# PERIPHERAL.net
KiCad netlist of a schematic drawn in Altium Designer
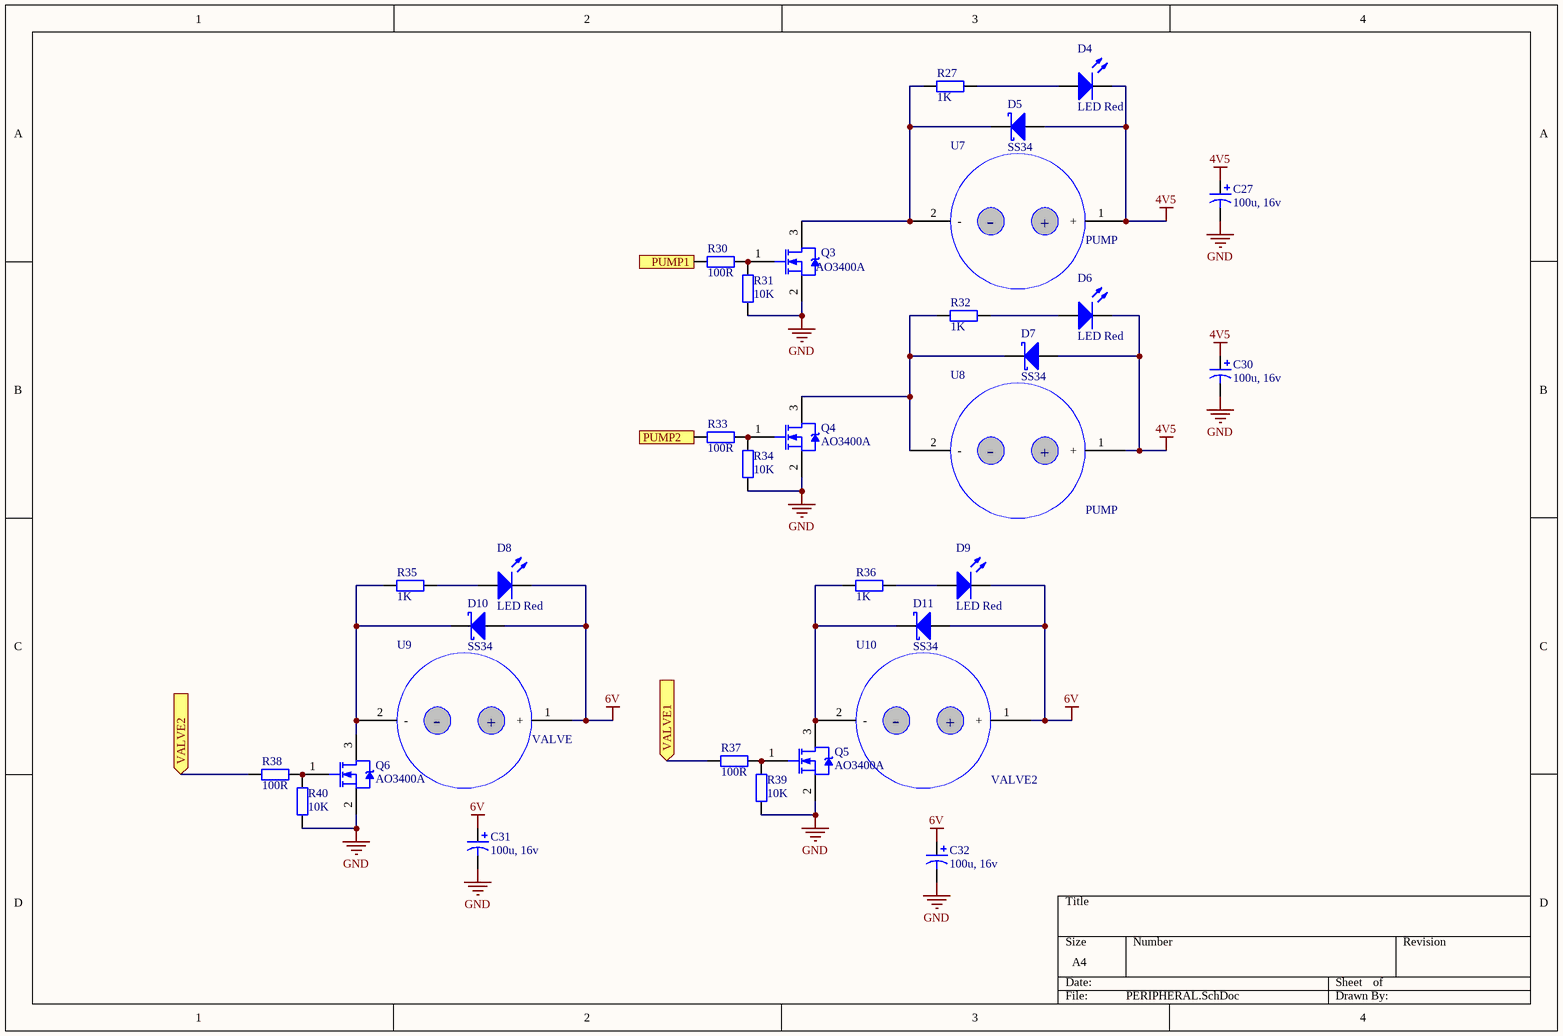
[diagram p0: PERIPHERAL.SchDoc]

(export (version "E")
  (design (tool "Eeschema 10.0.6"))
  (components
    (comp (ref "C27")
      (value "100u, 16v")
      (footprint "CAP-ALU-SMD-D")
      (description "CAP ALUM 100UF 20% 16V SMD")
      (libsource (lib "capacitor") (part "UWT1C101MCL1GB"))
    )
    (comp (ref "C30")
      (value "100u, 16v")
      (footprint "CAP-ALU-SMD-D")
      (description "CAP ALUM 100UF 20% 16V SMD")
      (libsource (lib "capacitor") (part "UWT1C101MCL1GB"))
    )
    (comp (ref "C31")
      (value "100u, 16v")
      (footprint "CAP-ALU-SMD-D")
      (description "CAP ALUM 100UF 20% 16V SMD")
      (libsource (lib "capacitor") (part "UWT1C101MCL1GB"))
    )
    (comp (ref "C32")
      (value "100u, 16v")
      (footprint "CAP-ALU-SMD-D")
      (description "CAP ALUM 100UF 20% 16V SMD")
      (libsource (lib "capacitor") (part "UWT1C101MCL1GB"))
    )
    (comp (ref "D4")
      (value "LED Red")
      (footprint "LED-0805-Red")
      (description "Lite-On LED Red 0603")
      (libsource (lib "diode") (part "LTST-C190KRKT"))
    )
    (comp (ref "D5")
      (value "SS34")
      (footprint "DIO-SMD-106")
      (description "Schottky Diode 40V 3A SMA")
      (libsource (lib "diode") (part "SS34"))
    )
    (comp (ref "D6")
      (value "LED Red")
      (footprint "LED-0805-Red")
      (description "Lite-On LED Red 0603")
      (libsource (lib "diode") (part "LTST-C190KRKT"))
    )
    (comp (ref "D7")
      (value "SS34")
      (footprint "DIO-SMD-106")
      (description "Schottky Diode 40V 3A SMA")
      (libsource (lib "diode") (part "SS34"))
    )
    (comp (ref "D8")
      (value "LED Red")
      (footprint "LED-0805-Red")
      (description "Lite-On LED Red 0603")
      (libsource (lib "diode") (part "LTST-C190KRKT"))
    )
    (comp (ref "D9")
      (value "LED Red")
      (footprint "LED-0805-Red")
      (description "Lite-On LED Red 0603")
      (libsource (lib "diode") (part "LTST-C190KRKT"))
    )
    (comp (ref "D10")
      (value "SS34")
      (footprint "DIO-SMD-106")
      (description "Schottky Diode 40V 3A SMA")
      (libsource (lib "diode") (part "SS34"))
    )
    (comp (ref "D11")
      (value "SS34")
      (footprint "DIO-SMD-106")
      (description "Schottky Diode 40V 3A SMA")
      (libsource (lib "diode") (part "SS34"))
    )
    (comp (ref "Q3")
      (value "AO3400A")
      (footprint "SOT-23-3L_AOS")
      (description "MOSFET N-CH 25V 5.8A SOT23")
      (libsource (lib "fet") (part "IRFML8244TRPBF"))
    )
    (comp (ref "Q4")
      (value "AO3400A")
      (footprint "SOT-23-3L_AOS-L")
      (description "MOSFET N-CH 25V 5.8A SOT23")
      (libsource (lib "fet") (part "IRFML8244TRPBF"))
    )
    (comp (ref "Q5")
      (value "AO3400A")
      (footprint "SOT-23-3L_AOS-L")
      (description "MOSFET N-CH 25V 5.8A SOT23")
      (libsource (lib "fet") (part "IRFML8244TRPBF"))
    )
    (comp (ref "Q6")
      (value "AO3400A")
      (footprint "SOT-23-3L_AOS-L")
      (description "MOSFET N-CH 25V 5.8A SOT23")
      (libsource (lib "fet") (part "IRFML8244TRPBF"))
    )
    (comp (ref "R27")
      (value "1K")
      (footprint "RES-SMD-0603")
      (description "Yageo RES 1K 5% 1/10W 0603")
      (fields (field (name "Comment") "RES 1K 5% 1/10W 0603"))
      (libsource (lib "resistor") (part "RC0603JR-071KL"))
    )
    (comp (ref "R30")
      (value "100R")
      (footprint "RES-SMD-0603")
      (description "Yageo RES 100R 5% 1/10W 0603")
      (fields (field (name "Comment") "RES 100R 5% 1/10W 0603"))
      (libsource (lib "resistor") (part "RC0603JR-07100RL"))
    )
    (comp (ref "R31")
      (value "10K")
      (footprint "RES-SMD-0603")
      (description "Yageo RES 10K 5% 1/10W 0603")
      (fields (field (name "Comment") "RES 10K 5% 1/10W 0603"))
      (libsource (lib "resistor") (part "RC0603JR-0710KL"))
    )
    (comp (ref "R32")
      (value "1K")
      (footprint "RES-SMD-0603")
      (description "Yageo RES 1K 5% 1/10W 0603")
      (fields (field (name "Comment") "RES 1K 5% 1/10W 0603"))
      (libsource (lib "resistor") (part "RC0603JR-071KL"))
    )
    (comp (ref "R33")
      (value "100R")
      (footprint "RES-SMD-0603")
      (description "Yageo RES 100R 5% 1/10W 0603")
      (fields (field (name "Comment") "RES 100R 5% 1/10W 0603"))
      (libsource (lib "resistor") (part "RC0603JR-07100RL"))
    )
    (comp (ref "R34")
      (value "10K")
      (footprint "RES-SMD-0603")
      (description "Yageo RES 10K 5% 1/10W 0603")
      (fields (field (name "Comment") "RES 10K 5% 1/10W 0603"))
      (libsource (lib "resistor") (part "RC0603JR-0710KL"))
    )
    (comp (ref "R35")
      (value "1K")
      (footprint "RES-SMD-0603")
      (description "Yageo RES 1K 5% 1/10W 0603")
      (fields (field (name "Comment") "RES 1K 5% 1/10W 0603"))
      (libsource (lib "resistor") (part "RC0603JR-071KL"))
    )
    (comp (ref "R36")
      (value "1K")
      (footprint "RES-SMD-0603")
      (description "Yageo RES 1K 5% 1/10W 0603")
      (fields (field (name "Comment") "RES 1K 5% 1/10W 0603"))
      (libsource (lib "resistor") (part "RC0603JR-071KL"))
    )
    (comp (ref "R37")
      (value "100R")
      (footprint "RES-SMD-0603")
      (description "Yageo RES 100R 5% 1/10W 0603")
      (fields (field (name "Comment") "RES 100R 5% 1/10W 0603"))
      (libsource (lib "resistor") (part "RC0603JR-07100RL"))
    )
    (comp (ref "R38")
      (value "100R")
      (footprint "RES-SMD-0603")
      (description "Yageo RES 100R 5% 1/10W 0603")
      (fields (field (name "Comment") "RES 100R 5% 1/10W 0603"))
      (libsource (lib "resistor") (part "RC0603JR-07100RL"))
    )
    (comp (ref "R39")
      (value "10K")
      (footprint "RES-SMD-0603")
      (description "Yageo RES 10K 5% 1/10W 0603")
      (fields (field (name "Comment") "RES 10K 5% 1/10W 0603"))
      (libsource (lib "resistor") (part "RC0603JR-0710KL"))
    )
    (comp (ref "R40")
      (value "10K")
      (footprint "RES-SMD-0603")
      (description "Yageo RES 10K 5% 1/10W 0603")
      (fields (field (name "Comment") "RES 10K 5% 1/10W 0603"))
      (libsource (lib "resistor") (part "RC0603JR-0710KL"))
    )
    (comp (ref "U7")
      (value "PUMP")
      (footprint "Pump")
      (description "Connector Header 2 Position 6.35mm Solder Straight Thru-Hole 2 Terminal 1 Port MLX-Series")
      (fields (field (name "MANUFACTURER") "Molex") (field (name "MANUFACTURER PART NUMBER") "10-84-4022"))
      (libsource (lib "LIB_PRESSURE") (part "A5F083"))
    )
    (comp (ref "U8")
      (value "PUMP")
      (footprint "Pump")
      (description "Connector Header 2 Position 6.35mm Solder Straight Thru-Hole 2 Terminal 1 Port MLX-Series")
      (fields (field (name "MANUFACTURER") "Molex") (field (name "MANUFACTURER PART NUMBER") "10-84-4022"))
      (libsource (lib "LIB_PRESSURE") (part "A5F083"))
    )
    (comp (ref "U9")
      (value "VALVE")
      (footprint "VALVE")
      (description "Connector Header 2 Position 6.35mm Solder Straight Thru-Hole 2 Terminal 1 Port MLX-Series")
      (fields (field (name "MANUFACTURER") "Molex") (field (name "MANUFACTURER PART NUMBER") "10-84-4022"))
      (libsource (lib "LIB_PRESSURE") (part "A5F083"))
    )
    (comp (ref "U10")
      (value "VALVE2")
      (footprint "VALVE")
      (description "Connector Header 2 Position 6.35mm Solder Straight Thru-Hole 2 Terminal 1 Port MLX-Series")
      (fields (field (name "MANUFACTURER") "Molex") (field (name "MANUFACTURER PART NUMBER") "10-84-4022"))
      (libsource (lib "LIB_PRESSURE") (part "A5F083"))
    )
  )
  (nets
    (net (code "1") (name "/PUMP1") (class "Default")
      (node (ref "R30") (pin "1") (pinfunction "1_1") (pintype "passive"))
    )
    (net (code "2") (name "/PUMP2") (class "Default")
      (node (ref "R33") (pin "1") (pinfunction "1_1") (pintype "passive"))
    )
    (net (code "3") (name "/VALVE1") (class "Default")
      (node (ref "R37") (pin "1") (pinfunction "1_1") (pintype "passive"))
    )
    (net (code "4") (name "/VALVE2") (class "Default")
      (node (ref "R38") (pin "1") (pinfunction "1_1") (pintype "passive"))
    )
    (net (code "5") (name "4V5") (class "Default")
      (node (ref "C27") (pin "1") (pinfunction "1_1") (pintype "passive"))
      (node (ref "C30") (pin "1") (pinfunction "1_1") (pintype "passive"))
      (node (ref "D4") (pin "2") (pinfunction "K_2") (pintype "passive"))
      (node (ref "D5") (pin "1") (pinfunction "A_1") (pintype "passive"))
      (node (ref "D6") (pin "2") (pinfunction "K_2") (pintype "passive"))
      (node (ref "D7") (pin "1") (pinfunction "A_1") (pintype "passive"))
      (node (ref "U7") (pin "1") (pinfunction "+_1") (pintype "passive"))
      (node (ref "U8") (pin "1") (pinfunction "+_1") (pintype "passive"))
    )
    (net (code "6") (name "6V") (class "Default")
      (node (ref "C31") (pin "1") (pinfunction "1_1") (pintype "passive"))
      (node (ref "C32") (pin "1") (pinfunction "1_1") (pintype "passive"))
      (node (ref "D10") (pin "1") (pinfunction "A_1") (pintype "passive"))
      (node (ref "D11") (pin "1") (pinfunction "A_1") (pintype "passive"))
      (node (ref "D8") (pin "2") (pinfunction "K_2") (pintype "passive"))
      (node (ref "D9") (pin "2") (pinfunction "K_2") (pintype "passive"))
      (node (ref "U10") (pin "1") (pinfunction "+_1") (pintype "passive"))
      (node (ref "U9") (pin "1") (pinfunction "+_1") (pintype "passive"))
    )
    (net (code "7") (name "GND") (class "Default")
      (node (ref "C27") (pin "2") (pinfunction "2_2") (pintype "passive"))
      (node (ref "C30") (pin "2") (pinfunction "2_2") (pintype "passive"))
      (node (ref "C31") (pin "2") (pinfunction "2_2") (pintype "passive"))
      (node (ref "C32") (pin "2") (pinfunction "2_2") (pintype "passive"))
      (node (ref "Q3") (pin "2") (pinfunction "S_2") (pintype "passive"))
      (node (ref "Q4") (pin "2") (pinfunction "S_2") (pintype "passive"))
      (node (ref "Q5") (pin "2") (pinfunction "S_2") (pintype "passive"))
      (node (ref "Q6") (pin "2") (pinfunction "S_2") (pintype "passive"))
      (node (ref "R31") (pin "1") (pinfunction "1_1") (pintype "passive"))
      (node (ref "R34") (pin "1") (pinfunction "1_1") (pintype "passive"))
      (node (ref "R39") (pin "1") (pinfunction "1_1") (pintype "passive"))
      (node (ref "R40") (pin "1") (pinfunction "1_1") (pintype "passive"))
    )
    (net (code "8") (name "Net-(D4-A)") (class "Default")
      (node (ref "D4") (pin "1") (pinfunction "A_1") (pintype "passive"))
      (node (ref "R27") (pin "2") (pinfunction "2_2") (pintype "passive"))
    )
    (net (code "9") (name "Net-(D5-K)") (class "Default")
      (node (ref "D5") (pin "2") (pinfunction "K_2") (pintype "passive"))
      (node (ref "Q3") (pin "3") (pinfunction "D_3") (pintype "passive"))
      (node (ref "R27") (pin "1") (pinfunction "1_1") (pintype "passive"))
      (node (ref "U7") (pin "2") (pinfunction "-_2") (pintype "passive"))
    )
    (net (code "10") (name "Net-(D6-A)") (class "Default")
      (node (ref "D6") (pin "1") (pinfunction "A_1") (pintype "passive"))
      (node (ref "R32") (pin "2") (pinfunction "2_2") (pintype "passive"))
    )
    (net (code "11") (name "Net-(D7-K)") (class "Default")
      (node (ref "D7") (pin "2") (pinfunction "K_2") (pintype "passive"))
      (node (ref "Q4") (pin "3") (pinfunction "D_3") (pintype "passive"))
      (node (ref "R32") (pin "1") (pinfunction "1_1") (pintype "passive"))
      (node (ref "U8") (pin "2") (pinfunction "-_2") (pintype "passive"))
    )
    (net (code "12") (name "Net-(D8-A)") (class "Default")
      (node (ref "D8") (pin "1") (pinfunction "A_1") (pintype "passive"))
      (node (ref "R35") (pin "2") (pinfunction "2_2") (pintype "passive"))
    )
    (net (code "13") (name "Net-(D9-A)") (class "Default")
      (node (ref "D9") (pin "1") (pinfunction "A_1") (pintype "passive"))
      (node (ref "R36") (pin "2") (pinfunction "2_2") (pintype "passive"))
    )
    (net (code "14") (name "Net-(D10-K)") (class "Default")
      (node (ref "D10") (pin "2") (pinfunction "K_2") (pintype "passive"))
      (node (ref "Q6") (pin "3") (pinfunction "D_3") (pintype "passive"))
      (node (ref "R35") (pin "1") (pinfunction "1_1") (pintype "passive"))
      (node (ref "U9") (pin "2") (pinfunction "-_2") (pintype "passive"))
    )
    (net (code "15") (name "Net-(D11-K)") (class "Default")
      (node (ref "D11") (pin "2") (pinfunction "K_2") (pintype "passive"))
      (node (ref "Q5") (pin "3") (pinfunction "D_3") (pintype "passive"))
      (node (ref "R36") (pin "1") (pinfunction "1_1") (pintype "passive"))
      (node (ref "U10") (pin "2") (pinfunction "-_2") (pintype "passive"))
    )
    (net (code "16") (name "Net-(Q3-G)") (class "Default")
      (node (ref "Q3") (pin "1") (pinfunction "G_1") (pintype "passive"))
      (node (ref "R30") (pin "2") (pinfunction "2_2") (pintype "passive"))
      (node (ref "R31") (pin "2") (pinfunction "2_2") (pintype "passive"))
    )
    (net (code "17") (name "Net-(Q4-G)") (class "Default")
      (node (ref "Q4") (pin "1") (pinfunction "G_1") (pintype "passive"))
      (node (ref "R33") (pin "2") (pinfunction "2_2") (pintype "passive"))
      (node (ref "R34") (pin "2") (pinfunction "2_2") (pintype "passive"))
    )
    (net (code "18") (name "Net-(Q5-G)") (class "Default")
      (node (ref "Q5") (pin "1") (pinfunction "G_1") (pintype "passive"))
      (node (ref "R37") (pin "2") (pinfunction "2_2") (pintype "passive"))
      (node (ref "R39") (pin "2") (pinfunction "2_2") (pintype "passive"))
    )
    (net (code "19") (name "Net-(Q6-G)") (class "Default")
      (node (ref "Q6") (pin "1") (pinfunction "G_1") (pintype "passive"))
      (node (ref "R38") (pin "2") (pinfunction "2_2") (pintype "passive"))
      (node (ref "R40") (pin "2") (pinfunction "2_2") (pintype "passive"))
    )
  )
)
